# microsd.net
KiCad netlist of a schematic drawn in EAGLE
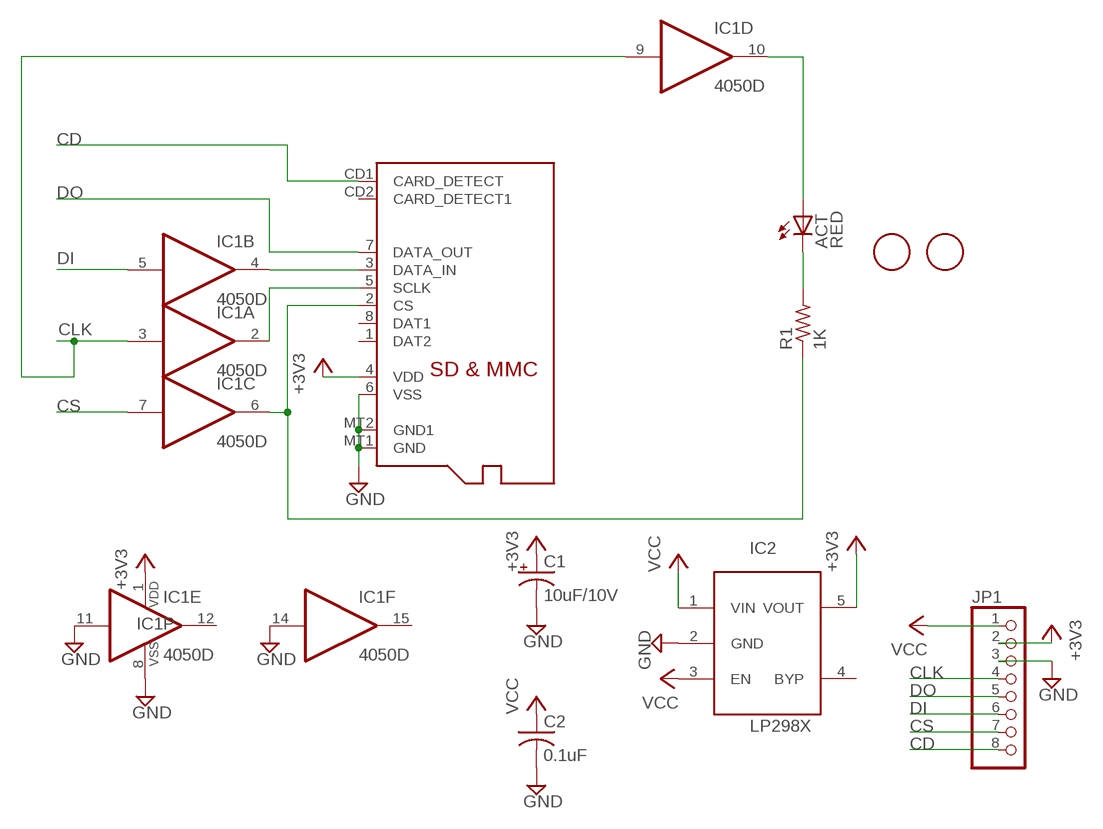
[diagram p0: schematic, sheet 1]

(export (version "E")
  (design (tool "Eeschema 10.0.6"))
  (components
    (comp (ref "ACT")
      (value "RED")
      (footprint "eagle-import:CHIP-LED0805")
      (libsource (lib "eagle-import") (part "LEDCHIP-LED0805"))
    )
    (comp (ref "C1")
      (value "10uF/10V")
      (footprint "eagle-import:A_3216-18R")
      (libsource (lib "eagle-import") (part "CPOL-USA/3216-18R"))
    )
    (comp (ref "C2")
      (value "0.1uF")
      (footprint "eagle-import:C0805K")
      (libsource (lib "eagle-import") (part "C-USC0805K"))
    )
    (comp (ref "IC1")
      (value "4050D")
      (footprint "eagle-import:SO16")
      (libsource (lib "eagle-import") (part "4050D"))
    )
    (comp (ref "IC2")
      (value "LP298XS")
      (footprint "eagle-import:SOT23-5L")
      (libsource (lib "eagle-import") (part "LP298XS"))
    )
    (comp (ref "JP1")
      (value "PINHD-1X8BIG")
      (footprint "eagle-import:1X08-BIG")
      (libsource (lib "eagle-import") (part "PINHD-1X8BIG"))
    )
    (comp (ref "R1")
      (value "1K")
      (footprint "eagle-import:R0805")
      (libsource (lib "eagle-import") (part "R-US_R0805"))
    )
    (comp (ref "U$1")
      (value "FIDUCIAL")
      (footprint "eagle-import:FIDUCIAL_1MM")
      (libsource (lib "eagle-import") (part "FIDUCIAL"))
    )
    (comp (ref "U$2")
      (value "FIDUCIAL")
      (footprint "eagle-import:FIDUCIAL_1MM")
      (libsource (lib "eagle-import") (part "FIDUCIAL"))
    )
    (comp (ref "X1")
      (value "MICROSD")
      (footprint "eagle-import:MICROSD")
      (libsource (lib "eagle-import") (part "MICROSD"))
    )
  )
  (nets
    (net (code "1") (name "+3V3") (class "Default")
      (node (ref "C1") (pin "+") (pinfunction "+_+") (pintype "passive"))
      (node (ref "IC1") (pin "1") (pinfunction "VDD_1") (pintype "power_in"))
      (node (ref "IC2") (pin "5") (pinfunction "VOUT_5") (pintype "bidirectional"))
      (node (ref "JP1") (pin "2") (pinfunction "2_2") (pintype "passive"))
      (node (ref "X1") (pin "4") (pinfunction "VDD_4") (pintype "power_in"))
    )
    (net (code "2") (name "/CD") (class "Default")
      (node (ref "JP1") (pin "8") (pinfunction "8_8") (pintype "passive"))
      (node (ref "X1") (pin "CD1") (pinfunction "CARD_DETECT_CD1") (pintype "passive"))
    )
    (net (code "3") (name "/CLK") (class "Default")
      (node (ref "IC1") (pin "3") (pinfunction "I_3") (pintype "input"))
      (node (ref "IC1") (pin "9") (pinfunction "I_9") (pintype "input"))
      (node (ref "JP1") (pin "4") (pinfunction "4_4") (pintype "passive"))
    )
    (net (code "4") (name "/CS") (class "Default")
      (node (ref "IC1") (pin "7") (pinfunction "I_7") (pintype "input"))
      (node (ref "JP1") (pin "7") (pinfunction "7_7") (pintype "passive"))
    )
    (net (code "5") (name "/DI") (class "Default")
      (node (ref "IC1") (pin "5") (pinfunction "I_5") (pintype "input"))
      (node (ref "JP1") (pin "6") (pinfunction "6_6") (pintype "passive"))
    )
    (net (code "6") (name "/DO") (class "Default")
      (node (ref "JP1") (pin "5") (pinfunction "5_5") (pintype "passive"))
      (node (ref "X1") (pin "7") (pinfunction "DATA_OUT_7") (pintype "output"))
    )
    (net (code "7") (name "GND") (class "Default")
      (node (ref "C1") (pin "-") (pinfunction "-_-") (pintype "passive"))
      (node (ref "C2") (pin "2") (pinfunction "2_2") (pintype "passive"))
      (node (ref "IC1") (pin "11") (pinfunction "I_11") (pintype "input"))
      (node (ref "IC1") (pin "14") (pinfunction "I_14") (pintype "input"))
      (node (ref "IC1") (pin "8") (pinfunction "VSS_8") (pintype "power_in"))
      (node (ref "IC2") (pin "2") (pinfunction "GND_2") (pintype "bidirectional"))
      (node (ref "JP1") (pin "3") (pinfunction "3_3") (pintype "passive"))
      (node (ref "X1") (pin "6") (pinfunction "VSS_6") (pintype "power_in"))
      (node (ref "X1") (pin "MT1") (pinfunction "GND_MT1") (pintype "power_in"))
      (node (ref "X1") (pin "MT2") (pinfunction "GND1_MT2") (pintype "power_in"))
    )
    (net (code "8") (name "Net-(ACT-PadC)") (class "Default")
      (node (ref "ACT") (pin "C") (pinfunction "C_C") (pintype "passive"))
      (node (ref "R1") (pin "2") (pinfunction "2_2") (pintype "passive"))
    )
    (net (code "9") (name "Net-(IC1A-O)") (class "Default")
      (node (ref "IC1") (pin "2") (pinfunction "O_2") (pintype "output"))
      (node (ref "X1") (pin "5") (pinfunction "SCLK_5") (pintype "input"))
    )
    (net (code "10") (name "Net-(IC1B-O)") (class "Default")
      (node (ref "IC1") (pin "4") (pinfunction "O_4") (pintype "output"))
      (node (ref "X1") (pin "3") (pinfunction "DATA_IN_3") (pintype "input"))
    )
    (net (code "11") (name "Net-(IC1C-O)") (class "Default")
      (node (ref "IC1") (pin "6") (pinfunction "O_6") (pintype "output"))
      (node (ref "R1") (pin "1") (pinfunction "1_1") (pintype "passive"))
      (node (ref "X1") (pin "2") (pinfunction "CS_2") (pintype "input"))
    )
    (net (code "12") (name "Net-(IC1D-O)") (class "Default")
      (node (ref "ACT") (pin "A") (pinfunction "A_A") (pintype "passive"))
      (node (ref "IC1") (pin "10") (pinfunction "O_10") (pintype "output"))
    )
    (net (code "13") (name "VCC") (class "Default")
      (node (ref "C2") (pin "1") (pinfunction "1_1") (pintype "passive"))
      (node (ref "IC2") (pin "1") (pinfunction "VIN_1") (pintype "bidirectional"))
      (node (ref "IC2") (pin "3") (pinfunction "EN_3") (pintype "bidirectional"))
      (node (ref "JP1") (pin "1") (pinfunction "1_1") (pintype "passive"))
    )
    (net (code "14") (name "unconnected-(IC1E-O-Pad12)") (class "Default")
      (node (ref "IC1") (pin "12") (pinfunction "O_12") (pintype "output"))
    )
    (net (code "15") (name "unconnected-(IC1F-O-Pad15)") (class "Default")
      (node (ref "IC1") (pin "15") (pinfunction "O_15") (pintype "output"))
    )
    (net (code "16") (name "unconnected-(IC2-BYP-Pad4)") (class "Default")
      (node (ref "IC2") (pin "4") (pinfunction "BYP_4") (pintype "bidirectional"))
    )
    (net (code "17") (name "unconnected-(X1-CARD_DETECT1-PadCD2)") (class "Default")
      (node (ref "X1") (pin "CD2") (pinfunction "CARD_DETECT1_CD2") (pintype "passive"))
    )
    (net (code "18") (name "unconnected-(X1-DAT1-Pad8)") (class "Default")
      (node (ref "X1") (pin "8") (pinfunction "DAT1_8") (pintype "bidirectional"))
    )
    (net (code "19") (name "unconnected-(X1-DAT2-Pad1)") (class "Default")
      (node (ref "X1") (pin "1") (pinfunction "DAT2_1") (pintype "bidirectional"))
    )
  )
)
